# ProProject_PetCareSTM32_MiniSTM32_2024-0.net
KiCad netlist of a schematic drawn in EasyEDA Pro
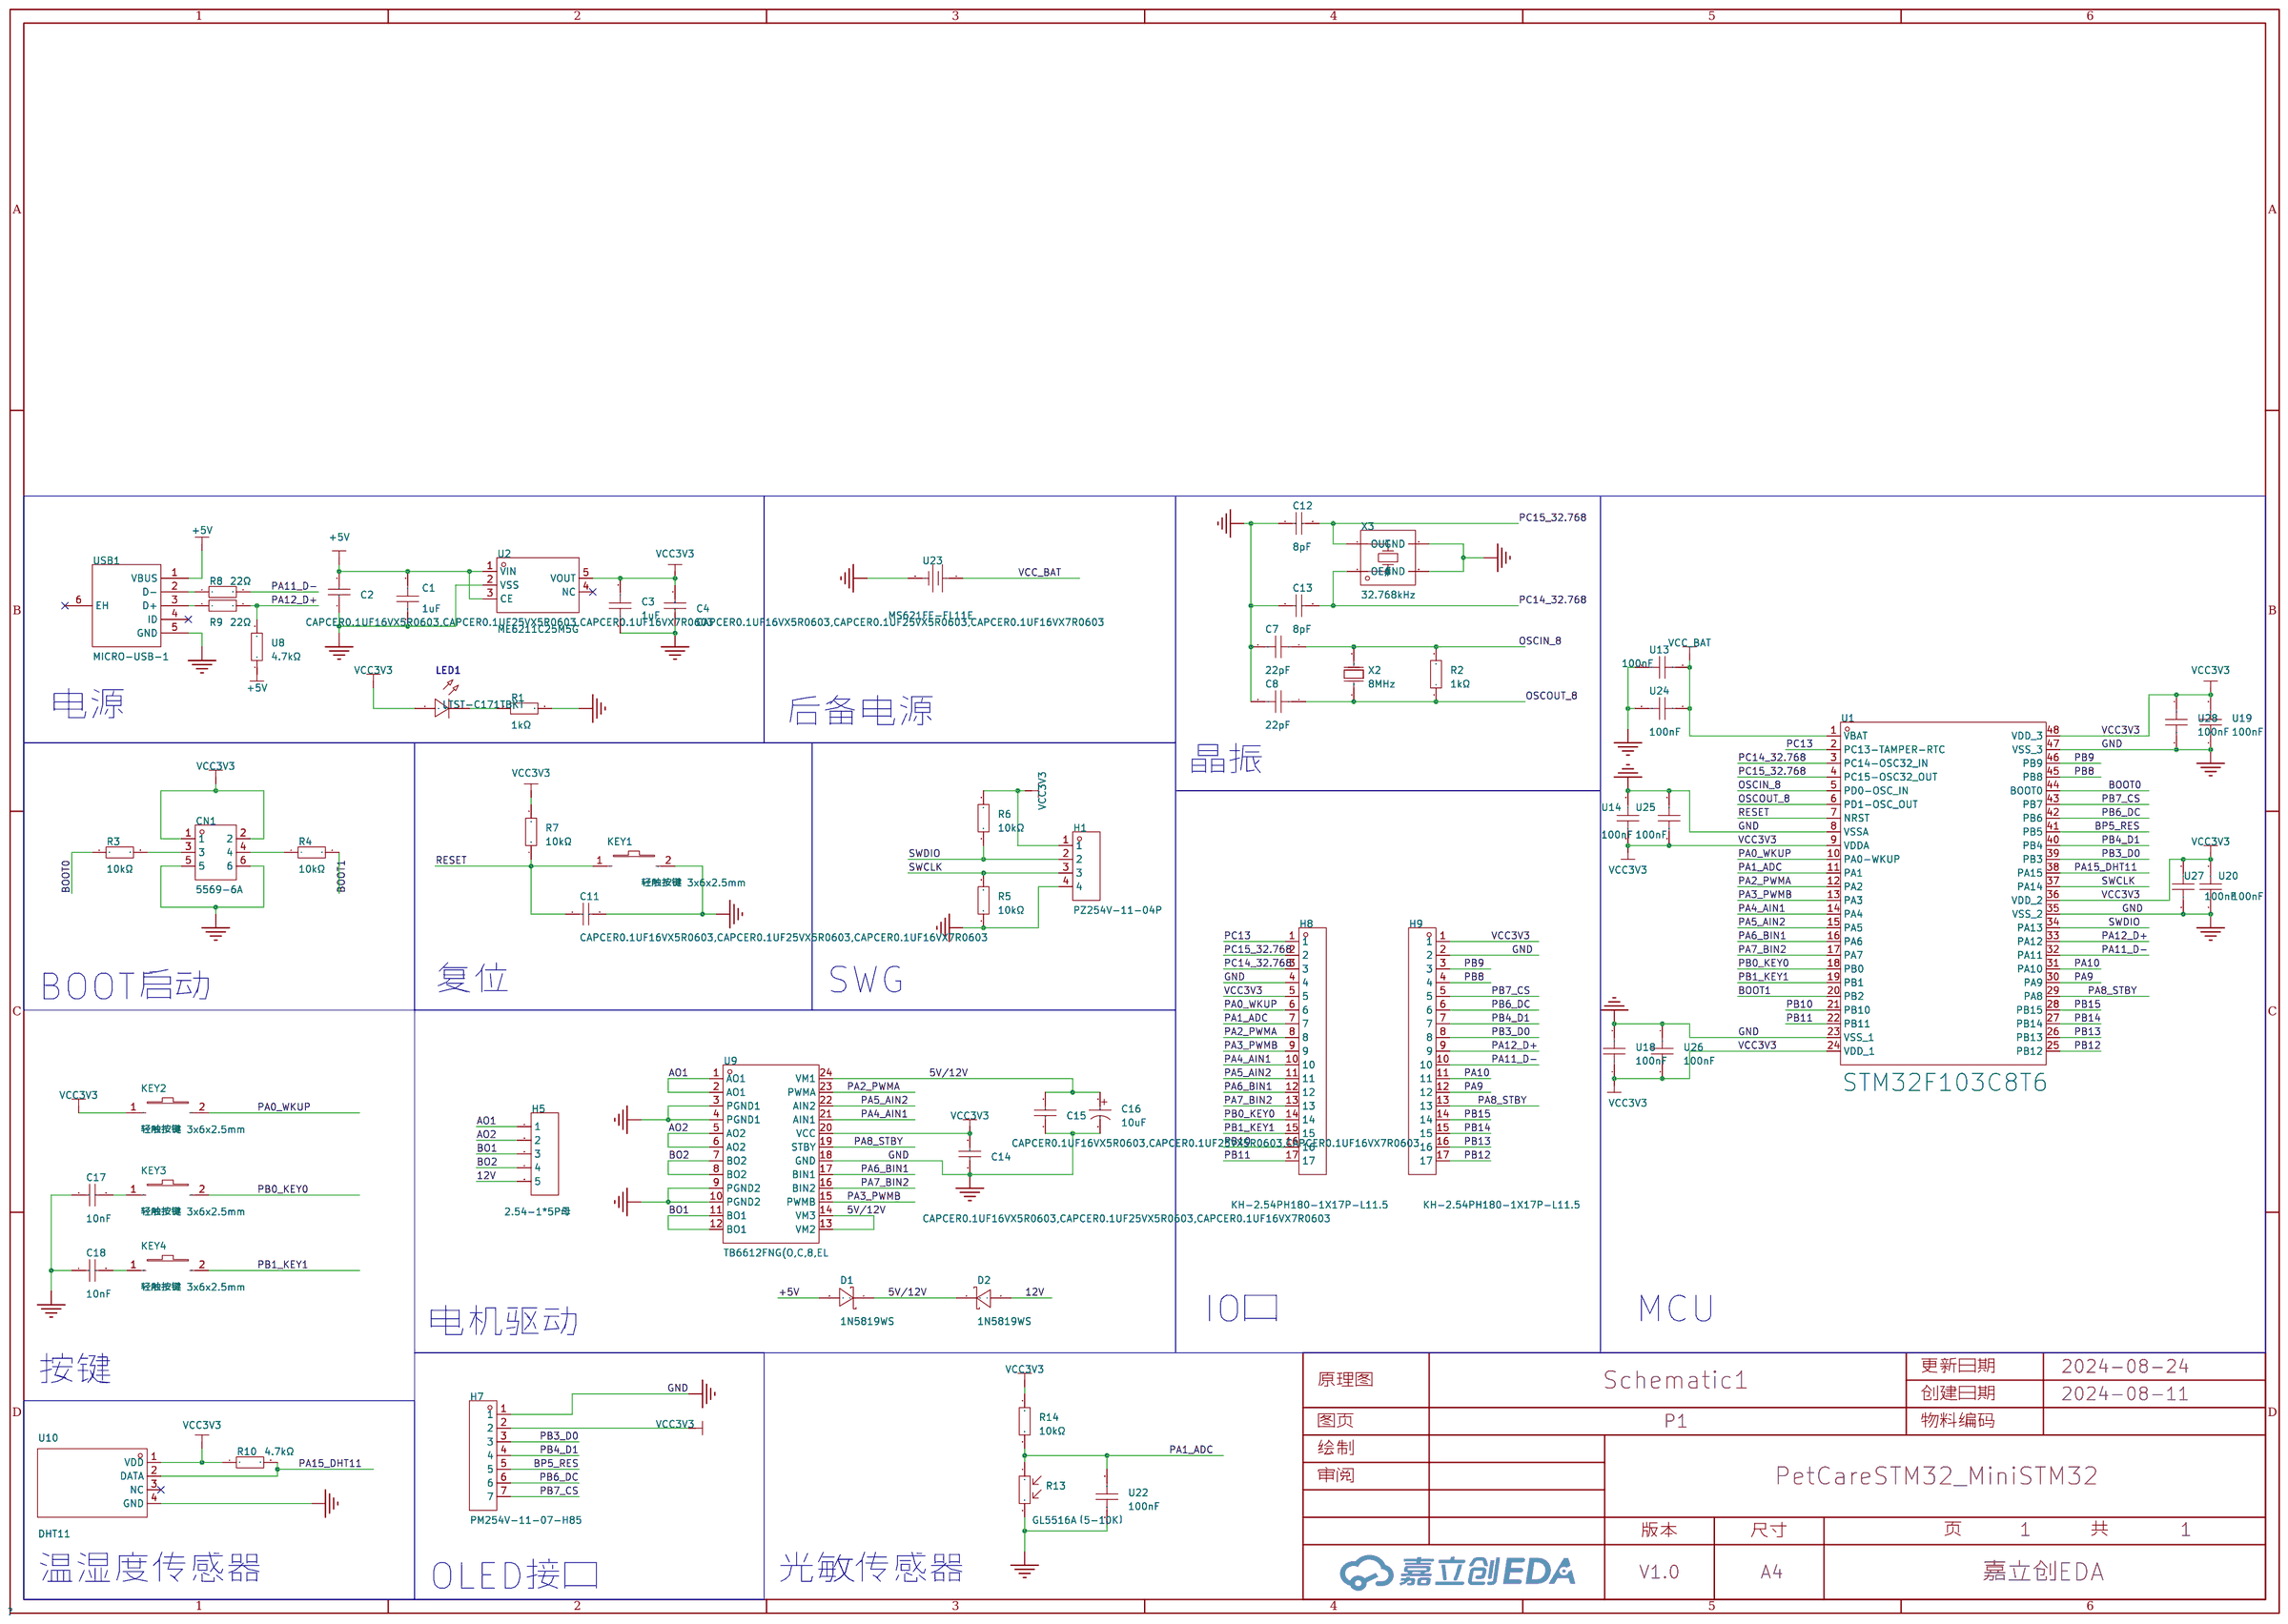
[diagram p0: schematic sheet]

(export (version "E")
  (design (tool "Eeschema 10.0.6"))
  (components
    (comp (ref "C1")
      (value "1uF")
      (footprint "easyedapro:C0603")
      (description "容值:1uF;精度:±10%;额定电压:50V;材质(温度系数):X5R;")
      (fields
        (field (name "Manufacturer Part") "CL10A105KB8NNNC")
        (field (name "Manufacturer") "SAMSUNG(三星)")
      )
      (libsource (lib "easyedapro") (part "CL10A105KB8NNNC"))
    )
    (comp (ref "C2")
      (value "CAPCER0.1UF16VX5R0603,CAPCER0.1UF25VX5R0603,CAPCER0.1UF16VX7R0603")
      (footprint "easyedapro:C0603")
      (libsource (lib "easyedapro") (part "CAPCER0.1UF16VX5R0603,CAPCER0.1UF25VX5R0603,CAPCER0.1UF16VX7R0603"))
    )
    (comp (ref "C3")
      (value "1uF")
      (footprint "easyedapro:C0603")
      (description "容值:1uF;精度:±10%;额定电压:50V;材质(温度系数):X5R;")
      (fields
        (field (name "Manufacturer Part") "CL10A105KB8NNNC")
        (field (name "Manufacturer") "SAMSUNG(三星)")
      )
      (libsource (lib "easyedapro") (part "CL10A105KB8NNNC"))
    )
    (comp (ref "C4")
      (value "CAPCER0.1UF16VX5R0603,CAPCER0.1UF25VX5R0603,CAPCER0.1UF16VX7R0603")
      (footprint "easyedapro:C0603")
      (libsource (lib "easyedapro") (part "CAPCER0.1UF16VX5R0603,CAPCER0.1UF25VX5R0603,CAPCER0.1UF16VX7R0603"))
    )
    (comp (ref "C7")
      (value "22pF")
      (footprint "easyedapro:C0603")
      (description "容值:22pF;精度:±5%;额定电压:50V;材质(温度系数):C0G;")
      (fields
        (field (name "Manufacturer Part") "CL10C220JB81PNC")
        (field (name "Manufacturer") "SAMSUNG(三星)")
      )
      (libsource (lib "easyedapro") (part "CL10C220JB81PNC"))
    )
    (comp (ref "C8")
      (value "22pF")
      (footprint "easyedapro:C0603")
      (description "容值:22pF;精度:±5%;额定电压:50V;材质(温度系数):C0G;")
      (fields
        (field (name "Manufacturer Part") "CL10C220JB81PNC")
        (field (name "Manufacturer") "SAMSUNG(三星)")
      )
      (libsource (lib "easyedapro") (part "CL10C220JB81PNC"))
    )
    (comp (ref "C11")
      (value "CAPCER0.1UF16VX5R0603,CAPCER0.1UF25VX5R0603,CAPCER0.1UF16VX7R0603")
      (footprint "easyedapro:C0603")
      (libsource (lib "easyedapro") (part "CAPCER0.1UF16VX5R0603,CAPCER0.1UF25VX5R0603,CAPCER0.1UF16VX7R0603"))
    )
    (comp (ref "C12")
      (value "8pF")
      (footprint "easyedapro:C0603")
      (description "容值:8pF;额定电压:50V;材质(温度系数):C0G;")
      (fields (field (name "Manufacturer Part") "0603CG8R0C500NT") (field (name "Manufacturer") "FH(风华)"))
      (libsource (lib "easyedapro") (part "0603CG8R0C500NT_C36508"))
    )
    (comp (ref "C13")
      (value "8pF")
      (footprint "easyedapro:C0603")
      (description "容值:8pF;额定电压:50V;材质(温度系数):C0G;")
      (fields (field (name "Manufacturer Part") "0603CG8R0C500NT") (field (name "Manufacturer") "FH(风华)"))
      (libsource (lib "easyedapro") (part "0603CG8R0C500NT_C36508"))
    )
    (comp (ref "C14")
      (value "CAPCER0.1UF16VX5R0603,CAPCER0.1UF25VX5R0603,CAPCER0.1UF16VX7R0603")
      (footprint "easyedapro:C0603")
      (libsource (lib "easyedapro") (part "CAPCER0.1UF16VX5R0603,CAPCER0.1UF25VX5R0603,CAPCER0.1UF16VX7R0603"))
    )
    (comp (ref "C15")
      (value "CAPCER0.1UF16VX5R0603,CAPCER0.1UF25VX5R0603,CAPCER0.1UF16VX7R0603")
      (footprint "easyedapro:C0603")
      (libsource (lib "easyedapro") (part "CAPCER0.1UF16VX5R0603,CAPCER0.1UF25VX5R0603,CAPCER0.1UF16VX7R0603"))
    )
    (comp (ref "C16")
      (value "10uF")
      (footprint "easyedapro:CAP-TH_BD5.0-P2.00-D0.8-FD")
      (description "容值:10uF;精度:±20%;额定电压:25V;")
      (fields (field (name "Manufacturer Part") "KF100M025C110A") (field (name "Manufacturer") "CapXon(丰宾)"))
      (libsource (lib "easyedapro") (part "KF100M025C110A"))
    )
    (comp (ref "C17")
      (value "10nF")
      (footprint "easyedapro:C0603")
      (description "容值:10nF;精度:±10%;额定电压:50V;材质(温度系数):X7R;")
      (fields
        (field (name "Manufacturer Part") "CC0603KRX7R9BB103")
        (field (name "Manufacturer") "YAGEO(国巨)")
      )
      (libsource (lib "easyedapro") (part "CC0603KRX7R9BB103"))
    )
    (comp (ref "C18")
      (value "10nF")
      (footprint "easyedapro:C0603")
      (description "容值:10nF;精度:±10%;额定电压:50V;材质(温度系数):X7R;")
      (fields
        (field (name "Manufacturer Part") "CC0603KRX7R9BB103")
        (field (name "Manufacturer") "YAGEO(国巨)")
      )
      (libsource (lib "easyedapro") (part "CC0603KRX7R9BB103"))
    )
    (comp (ref "CN1")
      (value "5569-6A")
      (footprint "easyedapro:CONN-TH_6P-P4.20_5569-6A-1")
      (libsource (lib "easyedapro") (part "5569-6A"))
    )
    (comp (ref "D1")
      (value "1N5819WS")
      (footprint "easyedapro:SOD-323_L1.8-W1.3-LS2.5-RD")
      (description "正向压降(Vf):600mV@1A;直流反向耐压(Vr):40V;平均整流电流(Io):1A;")
      (fields (field (name "Manufacturer") "Hottech(合科泰)"))
      (libsource (lib "easyedapro") (part "1N5819WS"))
    )
    (comp (ref "D2")
      (value "1N5819WS")
      (footprint "easyedapro:SOD-323_L1.8-W1.3-LS2.5-RD")
      (description "正向压降(Vf):600mV@1A;直流反向耐压(Vr):40V;平均整流电流(Io):1A;")
      (fields (field (name "Manufacturer") "Hottech(合科泰)"))
      (libsource (lib "easyedapro") (part "1N5819WS"))
    )
    (comp (ref "H1")
      (value "PZ254V-11-04P")
      (footprint "easyedapro:HDR-TH_4P-P2.54-V-M")
      (fields (field (name "Manufacturer") "XFCN(兴飞)"))
      (libsource (lib "easyedapro") (part "PZ254V-11-04P_C2691448"))
    )
    (comp (ref "H5")
      (value "2.54-1*5P母")
      (footprint "easyedapro:HDR-TH_5P-P2.54-V-F")
      (description "插孔结构:1x5P;间距:2.54mm;行距:-;安装类型:直插;排数:单排;总孔位数:5P;塑高:-;触头材质:-;触头镀层:-;")
      (fields (field (name "Manufacturer") "BOOMELE(博穆精密)"))
      (libsource (lib "easyedapro") (part "Header-Female-2.54_1x5"))
    )
    (comp (ref "H7")
      (value "PM254V-11-07-H85")
      (footprint "easyedapro:HDR-TH_7P-P2.54-V-F")
      (fields (field (name "Manufacturer") "XFCN(兴飞)"))
      (libsource (lib "easyedapro") (part "PM254V-11-07-H85"))
    )
    (comp (ref "H8")
      (value "KH-2.54PH180-1X17P-L11.5")
      (footprint "easyedapro:HDR-TH_17P-P2.54-V-M")
      (fields (field (name "Manufacturer") "kinghelm(金航标)"))
      (libsource (lib "easyedapro") (part "KH-2.54PH180-1X17P-L11.5"))
    )
    (comp (ref "H9")
      (value "KH-2.54PH180-1X17P-L11.5")
      (footprint "easyedapro:HDR-TH_17P-P2.54-V-M")
      (fields (field (name "Manufacturer") "kinghelm(金航标)"))
      (libsource (lib "easyedapro") (part "KH-2.54PH180-1X17P-L11.5"))
    )
    (comp (ref "KEY1")
      (value "轻触按键 3x6x2.5mm")
      (footprint "easyedapro:SW-SMD_L6.0-W3.6-LS8.0")
      (libsource (lib "easyedapro") (part "3x6x2.5mm"))
    )
    (comp (ref "KEY2")
      (value "轻触按键 3x6x2.5mm")
      (footprint "easyedapro:SW-SMD_L6.0-W3.6-LS8.0")
      (libsource (lib "easyedapro") (part "3x6x2.5mm"))
    )
    (comp (ref "KEY3")
      (value "轻触按键 3x6x2.5mm")
      (footprint "easyedapro:SW-SMD_L6.0-W3.6-LS8.0")
      (libsource (lib "easyedapro") (part "3x6x2.5mm"))
    )
    (comp (ref "KEY4")
      (value "轻触按键 3x6x2.5mm")
      (footprint "easyedapro:SW-SMD_L6.0-W3.6-LS8.0")
      (libsource (lib "easyedapro") (part "3x6x2.5mm"))
    )
    (comp (ref "LED1")
      (value "LTST-C171TBKT")
      (footprint "easyedapro:LED_0805")
      (fields (field (name "Manufacturer") "LITEON(光宝)"))
      (libsource (lib "easyedapro") (part "LED_B"))
    )
    (comp (ref "R1")
      (value "1kΩ")
      (footprint "easyedapro:R0603")
      (description "电阻类型:厚膜电阻;阻值:1kΩ;精度:±1%;功率:100mW;最大工作电压:75V;温度系数:±100ppm/°C;")
      (fields (field (name "Manufacturer Part") "RC0603FR-071KL") (field (name "Manufacturer") "YAGEO(国巨)"))
      (libsource (lib "easyedapro") (part "RC0603FR-071KL"))
    )
    (comp (ref "R2")
      (value "1kΩ")
      (footprint "easyedapro:R0603")
      (description "电阻类型:厚膜电阻;阻值:1kΩ;精度:±0.5%;功率:100mW;最大工作电压:75V;温度系数:±100ppm/°C;")
      (fields
        (field (name "Manufacturer Part") "0603WAD1001T5E")
        (field (name "Manufacturer") "UNI-ROYAL(厚声)")
      )
      (libsource (lib "easyedapro") (part "0603WAD1001T5E"))
    )
    (comp (ref "R3")
      (value "10kΩ")
      (footprint "easyedapro:R0603")
      (description "电阻类型:厚膜电阻;阻值:10kΩ;精度:±1%;功率:100mW;最大工作电压:75V;温度系数:±100ppm/°C;")
      (fields
        (field (name "Manufacturer Part") "0603WAF1002T5E")
        (field (name "Manufacturer") "UNI-ROYAL(厚声)")
      )
      (libsource (lib "easyedapro") (part "0603WAF1002T5E"))
    )
    (comp (ref "R4")
      (value "10kΩ")
      (footprint "easyedapro:R0603")
      (description "电阻类型:厚膜电阻;阻值:10kΩ;精度:±1%;功率:100mW;最大工作电压:75V;温度系数:±100ppm/°C;")
      (fields
        (field (name "Manufacturer Part") "0603WAF1002T5E")
        (field (name "Manufacturer") "UNI-ROYAL(厚声)")
      )
      (libsource (lib "easyedapro") (part "0603WAF1002T5E"))
    )
    (comp (ref "R5")
      (value "10kΩ")
      (footprint "easyedapro:R0603")
      (description "电阻类型:厚膜电阻;阻值:10kΩ;精度:±1%;功率:100mW;最大工作电压:75V;温度系数:±100ppm/°C;")
      (fields
        (field (name "Manufacturer Part") "0603WAF1002T5E")
        (field (name "Manufacturer") "UNI-ROYAL(厚声)")
      )
      (libsource (lib "easyedapro") (part "0603WAF1002T5E"))
    )
    (comp (ref "R6")
      (value "10kΩ")
      (footprint "easyedapro:R0603")
      (description "电阻类型:厚膜电阻;阻值:10kΩ;精度:±1%;功率:100mW;最大工作电压:75V;温度系数:±100ppm/°C;")
      (fields
        (field (name "Manufacturer Part") "0603WAF1002T5E")
        (field (name "Manufacturer") "UNI-ROYAL(厚声)")
      )
      (libsource (lib "easyedapro") (part "0603WAF1002T5E"))
    )
    (comp (ref "R7")
      (value "10kΩ")
      (footprint "easyedapro:R0603")
      (description "电阻类型:厚膜电阻;阻值:10kΩ;精度:±1%;功率:100mW;最大工作电压:75V;温度系数:±100ppm/°C;")
      (fields
        (field (name "Manufacturer Part") "0603WAF1002T5E")
        (field (name "Manufacturer") "UNI-ROYAL(厚声)")
      )
      (libsource (lib "easyedapro") (part "0603WAF1002T5E"))
    )
    (comp (ref "R8")
      (value "22Ω")
      (footprint "easyedapro:R0805")
      (description "电阻类型:薄膜电阻;阻值:22Ω;精度:±1%;功率:250mW;最大工作电压:150V;温度系数:±25ppm/°C;")
      (fields
        (field (name "Manufacturer Part") "TC0525F220JT5E")
        (field (name "Manufacturer") "UNI-ROYAL(厚声)")
      )
      (libsource (lib "easyedapro") (part "TC0525F220JT5E"))
    )
    (comp (ref "R9")
      (value "22Ω")
      (footprint "easyedapro:R0805")
      (description "电阻类型:薄膜电阻;阻值:22Ω;精度:±1%;功率:250mW;最大工作电压:150V;温度系数:±25ppm/°C;")
      (fields
        (field (name "Manufacturer Part") "TC0525F220JT5E")
        (field (name "Manufacturer") "UNI-ROYAL(厚声)")
      )
      (libsource (lib "easyedapro") (part "TC0525F220JT5E"))
    )
    (comp (ref "R10")
      (value "4.7kΩ")
      (footprint "easyedapro:R1206")
      (description "电阻类型:厚膜电阻;阻值:4.7kΩ;精度:±1%;功率:250mW;最大工作电压:200V;温度系数:±100ppm/°C;")
      (fields
        (field (name "Manufacturer Part") "1206W4F4701T5E")
        (field (name "Manufacturer") "UNI-ROYAL(厚声)")
      )
      (libsource (lib "easyedapro") (part "1206W4F4701T5E"))
    )
    (comp (ref "R13")
      (value "GL5516A（5-10K）")
      (footprint "easyedapro:RES-TH_L5.1-W4.3-P3.40_GL55")
      (description "暗电阻:200kΩ;亮电阻 @ 10Lux:5kΩ~10kΩ;光谱峰值(波长):540nm;")
      (fields (field (name "Manufacturer") "JCHL(晶创和立)"))
      (libsource (lib "easyedapro") (part "GL5516A(5-10K)"))
    )
    (comp (ref "R14")
      (value "10kΩ")
      (footprint "easyedapro:R0603")
      (description "电阻类型:厚膜电阻;阻值:10kΩ;精度:±1%;功率:100mW;最大工作电压:75V;温度系数:±100ppm/°C;")
      (fields
        (field (name "Manufacturer Part") "0603WAF1002T5E")
        (field (name "Manufacturer") "UNI-ROYAL(厚声)")
      )
      (libsource (lib "easyedapro") (part "0603WAF1002T5E"))
    )
    (comp (ref "U1")
      (value "STM32F103C8T6")
      (footprint "easyedapro:LQFP-48_L7.0-W7.0-P0.50-LS9.0-BL")
      (description "CPU内核:ARM-M3;程序存储容量:64KB;RAM总容量:20KB;GPIO端口数量:37;工作电压范围:2V~3.6V;CPU最大主频:72MHz;程序存储器类型:FLASH;")
      (fields (field (name "Manufacturer") "ST(意法半导体)"))
      (libsource (lib "easyedapro") (part "STM32F103C8T6"))
    )
    (comp (ref "U2")
      (value "ME6211C25M5G")
      (footprint "easyedapro:SOT-23-5_L2.9-W1.7-P0.95-LS2.8-BL")
      (fields (field (name "Manufacturer") "MICRONE(南京微盟)"))
      (libsource (lib "easyedapro") (part "ME6211C25M5G"))
    )
    (comp (ref "U8")
      (value "4.7kΩ")
      (footprint "easyedapro:R0603")
      (description "电阻类型:薄膜电阻;阻值:4.7kΩ;精度:±1%;功率:100mW;最大工作电压:75V;温度系数:±50ppm/°C;")
      (fields (field (name "Manufacturer Part") "AR03FTDX4701A") (field (name "Manufacturer") "Viking(光颉)"))
      (libsource (lib "easyedapro") (part "AR03FTDX4701A"))
    )
    (comp (ref "U9")
      (value "TB6612FNG(O,C,8,EL")
      (footprint "easyedapro:SSOP-24_L8.4-W5.8-P0.65-LS7.8-BL")
      (description "双直流电机驱动器集成电路")
      (fields (field (name "Manufacturer") "TOSHIBA(东芝)"))
      (libsource (lib "easyedapro") (part "TB6612FNG(O,C,8,EL"))
    )
    (comp (ref "U10")
      (value "DHT11")
      (footprint "easyedapro:SENSOR-TH_DHT11")
      (description "新款电容式数字温湿度传感器,老款已停产16.1x12.6x5.8mm")
      (fields (field (name "Manufacturer") "广州奥松"))
      (libsource (lib "easyedapro") (part "DHT11"))
    )
    (comp (ref "U13")
      (value "100nF")
      (footprint "easyedapro:C0603")
      (description "容值:100nF;精度:±10%;额定电压:50V;材质(温度系数):X7R;")
      (fields
        (field (name "Manufacturer Part") "CGA0603X7R104K500JT")
        (field (name "Manufacturer") "HRE(芯声)")
      )
      (libsource (lib "easyedapro") (part "CGA0603X7R104K500JT"))
    )
    (comp (ref "U14")
      (value "100nF")
      (footprint "easyedapro:C0603")
      (description "容值:100nF;精度:±10%;额定电压:50V;材质(温度系数):X7R;")
      (fields
        (field (name "Manufacturer Part") "CGA0603X7R104K500JT")
        (field (name "Manufacturer") "HRE(芯声)")
      )
      (libsource (lib "easyedapro") (part "CGA0603X7R104K500JT"))
    )
    (comp (ref "U18")
      (value "100nF")
      (footprint "easyedapro:C0603")
      (description "容值:100nF;精度:±10%;额定电压:50V;材质(温度系数):X7R;")
      (fields
        (field (name "Manufacturer Part") "CGA0603X7R104K500JT")
        (field (name "Manufacturer") "HRE(芯声)")
      )
      (libsource (lib "easyedapro") (part "CGA0603X7R104K500JT"))
    )
    (comp (ref "U19")
      (value "100nF")
      (footprint "easyedapro:C0603")
      (description "容值:100nF;精度:±10%;额定电压:50V;材质(温度系数):X7R;")
      (fields
        (field (name "Manufacturer Part") "CGA0603X7R104K500JT")
        (field (name "Manufacturer") "HRE(芯声)")
      )
      (libsource (lib "easyedapro") (part "CGA0603X7R104K500JT"))
    )
    (comp (ref "U20")
      (value "100nF")
      (footprint "easyedapro:C0603")
      (description "容值:100nF;精度:±10%;额定电压:50V;材质(温度系数):X7R;")
      (fields
        (field (name "Manufacturer Part") "CGA0603X7R104K500JT")
        (field (name "Manufacturer") "HRE(芯声)")
      )
      (libsource (lib "easyedapro") (part "CGA0603X7R104K500JT"))
    )
    (comp (ref "U22")
      (value "100nF")
      (footprint "easyedapro:C0603")
      (description "容值:100nF;精度:±10%;额定电压:50V;材质(温度系数):X7R;")
      (fields
        (field (name "Manufacturer Part") "CGA0603X7R104K500JT")
        (field (name "Manufacturer") "HRE(芯声)")
      )
      (libsource (lib "easyedapro") (part "CGA0603X7R104K500JT"))
    )
    (comp (ref "U23")
      (value "MS621FE-FL11E")
      (footprint "easyedapro:BAT-SMD_FL11E")
      (description "FL11E 3.3V可充电纽扣电池 5.5mAH")
      (fields (field (name "Manufacturer") "Seiko(精工)"))
      (libsource (lib "easyedapro") (part "MS621FE-FL11E"))
    )
    (comp (ref "U24")
      (value "100nF")
      (footprint "easyedapro:C0603")
      (description "容值:100nF;精度:±10%;额定电压:50V;材质(温度系数):X7R;")
      (fields
        (field (name "Manufacturer Part") "CGA0603X7R104K500JT")
        (field (name "Manufacturer") "HRE(芯声)")
      )
      (libsource (lib "easyedapro") (part "CGA0603X7R104K500JT"))
    )
    (comp (ref "U25")
      (value "100nF")
      (footprint "easyedapro:C0603")
      (description "容值:100nF;精度:±10%;额定电压:50V;材质(温度系数):X7R;")
      (fields
        (field (name "Manufacturer Part") "CGA0603X7R104K500JT")
        (field (name "Manufacturer") "HRE(芯声)")
      )
      (libsource (lib "easyedapro") (part "CGA0603X7R104K500JT"))
    )
    (comp (ref "U26")
      (value "100nF")
      (footprint "easyedapro:C0603")
      (description "容值:100nF;精度:±10%;额定电压:50V;材质(温度系数):X7R;")
      (fields
        (field (name "Manufacturer Part") "CGA0603X7R104K500JT")
        (field (name "Manufacturer") "HRE(芯声)")
      )
      (libsource (lib "easyedapro") (part "CGA0603X7R104K500JT"))
    )
    (comp (ref "U27")
      (value "100nF")
      (footprint "easyedapro:C0603")
      (description "容值:100nF;精度:±10%;额定电压:50V;材质(温度系数):X7R;")
      (fields
        (field (name "Manufacturer Part") "CGA0603X7R104K500JT")
        (field (name "Manufacturer") "HRE(芯声)")
      )
      (libsource (lib "easyedapro") (part "CGA0603X7R104K500JT"))
    )
    (comp (ref "U28")
      (value "100nF")
      (footprint "easyedapro:C0603")
      (description "容值:100nF;精度:±10%;额定电压:50V;材质(温度系数):X7R;")
      (fields
        (field (name "Manufacturer Part") "CGA0603X7R104K500JT")
        (field (name "Manufacturer") "HRE(芯声)")
      )
      (libsource (lib "easyedapro") (part "CGA0603X7R104K500JT"))
    )
    (comp (ref "USB1")
      (value "MICRO-USB-1")
      (footprint "easyedapro:MICRO-USB-SMD_C9900008946")
      (libsource (lib "easyedapro") (part "MICRO-USB-1"))
    )
    (comp (ref "X2")
      (value "8MHz")
      (footprint "easyedapro:OSC-SMD_L5.0-W3.2")
      (description "晶振类型:贴片晶振;频率:8MHz;常温频差:±20ppm;外接负载电容:18pF;频率稳定度(全温):±30ppm;")
      (fields
        (field (name "Manufacturer Part") "ABM3-8.000MHZ-D2Y-T")
        (field (name "Manufacturer") "ABRACON")
      )
      (libsource (lib "easyedapro") (part "ABM3-8.000MHZ-D2Y-T"))
    )
    (comp (ref "X3")
      (value "32.768kHz")
      (footprint "easyedapro:CRYSTAL-SMD_4P-L8.0-W3.8-BL")
      (description "晶振类型:-;频率:32.768kHz;常温频差:±20ppm;外接负载电容:12.5pF;频率稳定度(全温):-;")
      (fields (field (name "Manufacturer Part") "ABS25-32.768KHZ-T") (field (name "Manufacturer") "ABRACON"))
      (libsource (lib "easyedapro") (part "ABS25-32.768KHZ-T"))
    )
  )
  (nets
    (net (code "1") (name "+5V") (class "Default")
      (node (ref "C1") (pin "2") (pinfunction "2_2") (pintype "unspecified"))
      (node (ref "C2") (pin "2") (pinfunction "2_2") (pintype "input"))
      (node (ref "D1") (pin "2") (pinfunction "A_2") (pintype "unspecified"))
      (node (ref "U2") (pin "1") (pinfunction "VIN_1") (pintype "unspecified"))
      (node (ref "U2") (pin "3") (pinfunction "CE_3") (pintype "unspecified"))
      (node (ref "U8") (pin "1") (pinfunction "1_1") (pintype "unspecified"))
      (node (ref "USB1") (pin "1") (pinfunction "VBUS_1") (pintype "input"))
    )
    (net (code "2") (name "/5V{slash}12V") (class "Default")
      (node (ref "C15") (pin "2") (pinfunction "2_2") (pintype "input"))
      (node (ref "C16") (pin "1") (pinfunction "1_1") (pintype "input"))
      (node (ref "D1") (pin "1") (pinfunction "K_1") (pintype "unspecified"))
      (node (ref "D2") (pin "1") (pinfunction "K_1") (pintype "unspecified"))
      (node (ref "U9") (pin "13") (pinfunction "VM2_13") (pintype "unspecified"))
      (node (ref "U9") (pin "14") (pinfunction "VM3_14") (pintype "unspecified"))
      (node (ref "U9") (pin "24") (pinfunction "VM1_24") (pintype "unspecified"))
    )
    (net (code "3") (name "/12V") (class "Default")
      (node (ref "D2") (pin "2") (pinfunction "A_2") (pintype "unspecified"))
      (node (ref "H5") (pin "5") (pinfunction "5_5") (pintype "input"))
    )
    (net (code "4") (name "/AO1") (class "Default")
      (node (ref "H5") (pin "1") (pinfunction "1_1") (pintype "input"))
      (node (ref "U9") (pin "1") (pinfunction "AO1_1") (pintype "unspecified"))
      (node (ref "U9") (pin "2") (pinfunction "AO1_2") (pintype "unspecified"))
    )
    (net (code "5") (name "/AO2") (class "Default")
      (node (ref "H5") (pin "2") (pinfunction "2_2") (pintype "input"))
      (node (ref "U9") (pin "5") (pinfunction "AO2_5") (pintype "unspecified"))
      (node (ref "U9") (pin "6") (pinfunction "AO2_6") (pintype "unspecified"))
    )
    (net (code "6") (name "/BO1") (class "Default")
      (node (ref "H5") (pin "3") (pinfunction "3_3") (pintype "input"))
      (node (ref "U9") (pin "11") (pinfunction "BO1_11") (pintype "unspecified"))
      (node (ref "U9") (pin "12") (pinfunction "BO1_12") (pintype "unspecified"))
    )
    (net (code "7") (name "/BO2") (class "Default")
      (node (ref "H5") (pin "4") (pinfunction "4_4") (pintype "input"))
      (node (ref "U9") (pin "7") (pinfunction "BO2_7") (pintype "unspecified"))
      (node (ref "U9") (pin "8") (pinfunction "BO2_8") (pintype "unspecified"))
    )
    (net (code "8") (name "/BOOT0") (class "Default")
      (node (ref "R3") (pin "1") (pinfunction "1_1") (pintype "input"))
      (node (ref "U1") (pin "44") (pinfunction "BOOT0_44") (pintype "unspecified"))
    )
    (net (code "9") (name "/BOOT1") (class "Default")
      (node (ref "R4") (pin "2") (pinfunction "2_2") (pintype "input"))
      (node (ref "U1") (pin "20") (pinfunction "PB2_20") (pintype "unspecified"))
    )
    (net (code "10") (name "/BP5_RES") (class "Default")
      (node (ref "H7") (pin "5") (pinfunction "5_5") (pintype "unspecified"))
      (node (ref "U1") (pin "41") (pinfunction "PB5_41") (pintype "unspecified"))
    )
    (net (code "11") (name "/OSCIN_8") (class "Default")
      (node (ref "C7") (pin "1") (pinfunction "1_1") (pintype "unspecified"))
      (node (ref "R2") (pin "2") (pinfunction "2_2") (pintype "input"))
      (node (ref "U1") (pin "5") (pinfunction "PD0-OSC_IN_5") (pintype "unspecified"))
      (node (ref "X2") (pin "2") (pinfunction "OSC2_2") (pintype "input"))
    )
    (net (code "12") (name "/OSCOUT_8") (class "Default")
      (node (ref "C8") (pin "1") (pinfunction "1_1") (pintype "unspecified"))
      (node (ref "R2") (pin "1") (pinfunction "1_1") (pintype "input"))
      (node (ref "U1") (pin "6") (pinfunction "PD1-OSC_OUT_6") (pintype "unspecified"))
      (node (ref "X2") (pin "1") (pinfunction "OSC1_1") (pintype "input"))
    )
    (net (code "13") (name "/PA0_WKUP") (class "Default")
      (node (ref "H8") (pin "6") (pinfunction "6_6") (pintype "unspecified"))
      (node (ref "KEY2") (pin "2") (pinfunction "2_2") (pintype "input"))
      (node (ref "U1") (pin "10") (pinfunction "PA0-WKUP_10") (pintype "unspecified"))
    )
    (net (code "14") (name "/PA1_ADC") (class "Default")
      (node (ref "H8") (pin "7") (pinfunction "7_7") (pintype "unspecified"))
      (node (ref "R13") (pin "1") (pinfunction "1_1") (pintype "input"))
      (node (ref "R14") (pin "1") (pinfunction "1_1") (pintype "input"))
      (node (ref "U1") (pin "11") (pinfunction "PA1_11") (pintype "unspecified"))
      (node (ref "U22") (pin "2") (pinfunction "2_2") (pintype "unspecified"))
    )
    (net (code "15") (name "/PA2_PWMA") (class "Default")
      (node (ref "H8") (pin "8") (pinfunction "8_8") (pintype "unspecified"))
      (node (ref "U1") (pin "12") (pinfunction "PA2_12") (pintype "unspecified"))
      (node (ref "U9") (pin "23") (pinfunction "PWMA_23") (pintype "unspecified"))
    )
    (net (code "16") (name "/PA3_PWMB") (class "Default")
      (node (ref "H8") (pin "9") (pinfunction "9_9") (pintype "unspecified"))
      (node (ref "U1") (pin "13") (pinfunction "PA3_13") (pintype "unspecified"))
      (node (ref "U9") (pin "15") (pinfunction "PWMB_15") (pintype "unspecified"))
    )
    (net (code "17") (name "/PA4_AIN1") (class "Default")
      (node (ref "H8") (pin "10") (pinfunction "10_10") (pintype "unspecified"))
      (node (ref "U1") (pin "14") (pinfunction "PA4_14") (pintype "unspecified"))
      (node (ref "U9") (pin "21") (pinfunction "AIN1_21") (pintype "unspecified"))
    )
    (net (code "18") (name "/PA5_AIN2") (class "Default")
      (node (ref "H8") (pin "11") (pinfunction "11_11") (pintype "unspecified"))
      (node (ref "U1") (pin "15") (pinfunction "PA5_15") (pintype "unspecified"))
      (node (ref "U9") (pin "22") (pinfunction "AIN2_22") (pintype "unspecified"))
    )
    (net (code "19") (name "/PA6_BIN1") (class "Default")
      (node (ref "H8") (pin "12") (pinfunction "12_12") (pintype "unspecified"))
      (node (ref "U1") (pin "16") (pinfunction "PA6_16") (pintype "unspecified"))
      (node (ref "U9") (pin "17") (pinfunction "BIN1_17") (pintype "unspecified"))
    )
    (net (code "20") (name "/PA7_BIN2") (class "Default")
      (node (ref "H8") (pin "13") (pinfunction "13_13") (pintype "unspecified"))
      (node (ref "U1") (pin "17") (pinfunction "PA7_17") (pintype "unspecified"))
      (node (ref "U9") (pin "16") (pinfunction "BIN2_16") (pintype "unspecified"))
    )
    (net (code "21") (name "/PA8_STBY") (class "Default")
      (node (ref "H9") (pin "13") (pinfunction "13_13") (pintype "unspecified"))
      (node (ref "U1") (pin "29") (pinfunction "PA8_29") (pintype "unspecified"))
      (node (ref "U9") (pin "19") (pinfunction "STBY_19") (pintype "unspecified"))
    )
    (net (code "22") (name "/PA9") (class "Default")
      (node (ref "H9") (pin "12") (pinfunction "12_12") (pintype "unspecified"))
      (node (ref "U1") (pin "30") (pinfunction "PA9_30") (pintype "unspecified"))
    )
    (net (code "23") (name "/PA10") (class "Default")
      (node (ref "H9") (pin "11") (pinfunction "11_11") (pintype "unspecified"))
      (node (ref "U1") (pin "31") (pinfunction "PA10_31") (pintype "unspecified"))
    )
    (net (code "24") (name "/PA11_D-") (class "Default")
      (node (ref "H9") (pin "10") (pinfunction "10_10") (pintype "unspecified"))
      (node (ref "R8") (pin "2") (pinfunction "2_2") (pintype "input"))
      (node (ref "U1") (pin "32") (pinfunction "PA11_32") (pintype "unspecified"))
    )
    (net (code "25") (name "/PA12_D+") (class "Default")
      (node (ref "H9") (pin "9") (pinfunction "9_9") (pintype "unspecified"))
      (node (ref "R9") (pin "2") (pinfunction "2_2") (pintype "input"))
      (node (ref "U1") (pin "33") (pinfunction "PA12_33") (pintype "unspecified"))
      (node (ref "U8") (pin "2") (pinfunction "2_2") (pintype "unspecified"))
    )
    (net (code "26") (name "/PA15_DHT11") (class "Default")
      (node (ref "R10") (pin "2") (pinfunction "2_2") (pintype "input"))
      (node (ref "U1") (pin "38") (pinfunction "PA15_38") (pintype "unspecified"))
      (node (ref "U10") (pin "2") (pinfunction "DATA_2") (pintype "unspecified"))
    )
    (net (code "27") (name "/PB0_KEY0") (class "Default")
      (node (ref "H8") (pin "14") (pinfunction "14_14") (pintype "unspecified"))
      (node (ref "KEY3") (pin "2") (pinfunction "2_2") (pintype "input"))
      (node (ref "U1") (pin "18") (pinfunction "PB0_18") (pintype "unspecified"))
    )
    (net (code "28") (name "/PB1_KEY1") (class "Default")
      (node (ref "H8") (pin "15") (pinfunction "15_15") (pintype "unspecified"))
      (node (ref "KEY4") (pin "2") (pinfunction "2_2") (pintype "input"))
      (node (ref "U1") (pin "19") (pinfunction "PB1_19") (pintype "unspecified"))
    )
    (net (code "29") (name "/PB3_D0") (class "Default")
      (node (ref "H7") (pin "3") (pinfunction "3_3") (pintype "unspecified"))
      (node (ref "H9") (pin "8") (pinfunction "8_8") (pintype "unspecified"))
      (node (ref "U1") (pin "39") (pinfunction "PB3_39") (pintype "unspecified"))
    )
    (net (code "30") (name "/PB4_D1") (class "Default")
      (node (ref "H7") (pin "4") (pinfunction "4_4") (pintype "unspecified"))
      (node (ref "H9") (pin "7") (pinfunction "7_7") (pintype "unspecified"))
      (node (ref "U1") (pin "40") (pinfunction "PB4_40") (pintype "unspecified"))
    )
    (net (code "31") (name "/PB6_DC") (class "Default")
      (node (ref "H7") (pin "6") (pinfunction "6_6") (pintype "unspecified"))
      (node (ref "H9") (pin "6") (pinfunction "6_6") (pintype "unspecified"))
      (node (ref "U1") (pin "42") (pinfunction "PB6_42") (pintype "unspecified"))
    )
    (net (code "32") (name "/PB7_CS") (class "Default")
      (node (ref "H7") (pin "7") (pinfunction "7_7") (pintype "unspecified"))
      (node (ref "H9") (pin "5") (pinfunction "5_5") (pintype "unspecified"))
      (node (ref "U1") (pin "43") (pinfunction "PB7_43") (pintype "unspecified"))
    )
    (net (code "33") (name "/PB8") (class "Default")
      (node (ref "H9") (pin "4") (pinfunction "4_4") (pintype "unspecified"))
      (node (ref "U1") (pin "45") (pinfunction "PB8_45") (pintype "unspecified"))
    )
    (net (code "34") (name "/PB9") (class "Default")
      (node (ref "H9") (pin "3") (pinfunction "3_3") (pintype "unspecified"))
      (node (ref "U1") (pin "46") (pinfunction "PB9_46") (pintype "unspecified"))
    )
    (net (code "35") (name "/PB10") (class "Default")
      (node (ref "H8") (pin "16") (pinfunction "16_16") (pintype "unspecified"))
      (node (ref "U1") (pin "21") (pinfunction "PB10_21") (pintype "unspecified"))
    )
    (net (code "36") (name "/PB11") (class "Default")
      (node (ref "H8") (pin "17") (pinfunction "17_17") (pintype "unspecified"))
      (node (ref "U1") (pin "22") (pinfunction "PB11_22") (pintype "unspecified"))
    )
    (net (code "37") (name "/PB12") (class "Default")
      (node (ref "H9") (pin "17") (pinfunction "17_17") (pintype "unspecified"))
      (node (ref "U1") (pin "25") (pinfunction "PB12_25") (pintype "unspecified"))
    )
    (net (code "38") (name "/PB13") (class "Default")
      (node (ref "H9") (pin "16") (pinfunction "16_16") (pintype "unspecified"))
      (node (ref "U1") (pin "26") (pinfunction "PB13_26") (pintype "unspecified"))
    )
    (net (code "39") (name "/PB14") (class "Default")
      (node (ref "H9") (pin "15") (pinfunction "15_15") (pintype "unspecified"))
      (node (ref "U1") (pin "27") (pinfunction "PB14_27") (pintype "unspecified"))
    )
    (net (code "40") (name "/PB15") (class "Default")
      (node (ref "H9") (pin "14") (pinfunction "14_14") (pintype "unspecified"))
      (node (ref "U1") (pin "28") (pinfunction "PB15_28") (pintype "unspecified"))
    )
    (net (code "41") (name "/PC13") (class "Default")
      (node (ref "H8") (pin "1") (pinfunction "1_1") (pintype "unspecified"))
      (node (ref "U1") (pin "2") (pinfunction "PC13-TAMPER-RTC_2") (pintype "unspecified"))
    )
    (net (code "42") (name "/PC14_32.768") (class "Default")
      (node (ref "C13") (pin "2") (pinfunction "2_2") (pintype "input"))
      (node (ref "H8") (pin "3") (pinfunction "3_3") (pintype "unspecified"))
      (node (ref "U1") (pin "3") (pinfunction "PC14-OSC32_IN_3") (pintype "unspecified"))
      (node (ref "X3") (pin "1") (pinfunction "OE#_1") (pintype "input"))
    )
    (net (code "43") (name "/PC15_32.768") (class "Default")
      (node (ref "C12") (pin "2") (pinfunction "2_2") (pintype "input"))
      (node (ref "H8") (pin "2") (pinfunction "2_2") (pintype "unspecified"))
      (node (ref "U1") (pin "4") (pinfunction "PC15-OSC32_OUT_4") (pintype "unspecified"))
      (node (ref "X3") (pin "4") (pinfunction "OUT_4") (pintype "input"))
    )
    (net (code "44") (name "/RESET") (class "Default")
      (node (ref "C11") (pin "1") (pinfunction "1_1") (pintype "input"))
      (node (ref "KEY1") (pin "1") (pinfunction "1_1") (pintype "input"))
      (node (ref "R7") (pin "1") (pinfunction "1_1") (pintype "input"))
      (node (ref "U1") (pin "7") (pinfunction "NRST_7") (pintype "unspecified"))
    )
    (net (code "45") (name "/SWCLK") (class "Default")
      (node (ref "H1") (pin "3") (pinfunction "3_3") (pintype "unspecified"))
      (node (ref "R5") (pin "2") (pinfunction "2_2") (pintype "input"))
      (node (ref "U1") (pin "37") (pinfunction "PA14_37") (pintype "unspecified"))
    )
    (net (code "46") (name "/SWDIO") (class "Default")
      (node (ref "H1") (pin "2") (pinfunction "2_2") (pintype "unspecified"))
      (node (ref "R6") (pin "1") (pinfunction "1_1") (pintype "input"))
      (node (ref "U1") (pin "34") (pinfunction "PA13_34") (pintype "unspecified"))
    )
    (net (code "47") (name "GND") (class "Default")
      (node (ref "C1") (pin "1") (pinfunction "1_1") (pintype "unspecified"))
      (node (ref "C11") (pin "2") (pinfunction "2_2") (pintype "input"))
      (node (ref "C12") (pin "1") (pinfunction "1_1") (pintype "input"))
      (node (ref "C13") (pin "1") (pinfunction "1_1") (pintype "input"))
      (node (ref "C14") (pin "1") (pinfunction "1_1") (pintype "input"))
      (node (ref "C15") (pin "1") (pinfunction "1_1") (pintype "input"))
      (node (ref "C16") (pin "2") (pinfunction "2_2") (pintype "input"))
      (node (ref "C17") (pin "2") (pinfunction "2_2") (pintype "input"))
      (node (ref "C18") (pin "1") (pinfunction "1_1") (pintype "input"))
      (node (ref "C2") (pin "1") (pinfunction "1_1") (pintype "input"))
      (node (ref "C3") (pin "1") (pinfunction "1_1") (pintype "unspecified"))
      (node (ref "C4") (pin "1") (pinfunction "1_1") (pintype "input"))
      (node (ref "C7") (pin "2") (pinfunction "2_2") (pintype "unspecified"))
      (node (ref "C8") (pin "2") (pinfunction "2_2") (pintype "unspecified"))
      (node (ref "CN1") (pin "5") (pinfunction "5_5") (pintype "unspecified"))
      (node (ref "CN1") (pin "6") (pinfunction "6_6") (pintype "unspecified"))
      (node (ref "H1") (pin "4") (pinfunction "4_4") (pintype "unspecified"))
      (node (ref "H7") (pin "1") (pinfunction "1_1") (pintype "unspecified"))
      (node (ref "H8") (pin "4") (pinfunction "4_4") (pintype "unspecified"))
      (node (ref "H9") (pin "2") (pinfunction "2_2") (pintype "unspecified"))
      (node (ref "KEY1") (pin "2") (pinfunction "2_2") (pintype "input"))
      (node (ref "R1") (pin "2") (pinfunction "2_2") (pintype "input"))
      (node (ref "R13") (pin "2") (pinfunction "2_2") (pintype "input"))
      (node (ref "R5") (pin "1") (pinfunction "1_1") (pintype "input"))
      (node (ref "U1") (pin "23") (pinfunction "VSS_1_23") (pintype "unspecified"))
      (node (ref "U1") (pin "35") (pinfunction "VSS_2_35") (pintype "unspecified"))
      (node (ref "U1") (pin "47") (pinfunction "VSS_3_47") (pintype "unspecified"))
      (node (ref "U1") (pin "8") (pinfunction "VSSA_8") (pintype "unspecified"))
      (node (ref "U10") (pin "4") (pinfunction "GND_4") (pintype "unspecified"))
      (node (ref "U13") (pin "2") (pinfunction "2_2") (pintype "unspecified"))
      (node (ref "U14") (pin "2") (pinfunction "2_2") (pintype "unspecified"))
      (node (ref "U18") (pin "2") (pinfunction "2_2") (pintype "unspecified"))
      (node (ref "U19") (pin "1") (pinfunction "1_1") (pintype "unspecified"))
      (node (ref "U2") (pin "2") (pinfunction "VSS_2") (pintype "unspecified"))
      (node (ref "U20") (pin "1") (pinfunction "1_1") (pintype "unspecified"))
      (node (ref "U22") (pin "1") (pinfunction "1_1") (pintype "unspecified"))
      (node (ref "U23") (pin "2") (pinfunction "-_2") (pintype "unspecified"))
      (node (ref "U24") (pin "2") (pinfunction "2_2") (pintype "unspecified"))
      (node (ref "U25") (pin "1") (pinfunction "1_1") (pintype "unspecified"))
      (node (ref "U26") (pin "1") (pinfunction "1_1") (pintype "unspecified"))
      (node (ref "U27") (pin "2") (pinfunction "2_2") (pintype "unspecified"))
      (node (ref "U28") (pin "2") (pinfunction "2_2") (pintype "unspecified"))
      (node (ref "U9") (pin "10") (pinfunction "PGND2_10") (pintype "unspecified"))
      (node (ref "U9") (pin "18") (pinfunction "GND_18") (pintype "unspecified"))
      (node (ref "U9") (pin "3") (pinfunction "PGND1_3") (pintype "unspecified"))
      (node (ref "U9") (pin "4") (pinfunction "PGND1_4") (pintype "unspecified"))
      (node (ref "U9") (pin "9") (pinfunction "PGND2_9") (pintype "unspecified"))
      (node (ref "USB1") (pin "5") (pinfunction "GND_5") (pintype "input"))
      (node (ref "X3") (pin "2") (pinfunction "GND_2") (pintype "input"))
      (node (ref "X3") (pin "3") (pinfunction "GND_3") (pintype "input"))
    )
    (net (code "48") (name "Net-(C17-Pad1)") (class "Default")
      (node (ref "C17") (pin "1") (pinfunction "1_1") (pintype "input"))
      (node (ref "KEY3") (pin "1") (pinfunction "1_1") (pintype "input"))
    )
    (net (code "49") (name "Net-(C18-Pad2)") (class "Default")
      (node (ref "C18") (pin "2") (pinfunction "2_2") (pintype "input"))
      (node (ref "KEY4") (pin "1") (pinfunction "1_1") (pintype "input"))
    )
    (net (code "50") (name "Net-(CN1-Pad3)") (class "Default")
      (node (ref "CN1") (pin "3") (pinfunction "3_3") (pintype "unspecified"))
      (node (ref "R3") (pin "2") (pinfunction "2_2") (pintype "input"))
    )
    (net (code "51") (name "Net-(CN1-Pad4)") (class "Default")
      (node (ref "CN1") (pin "4") (pinfunction "4_4") (pintype "unspecified"))
      (node (ref "R4") (pin "1") (pinfunction "1_1") (pintype "input"))
    )
    (net (code "52") (name "Net-(LED1-C)") (class "Default")
      (node (ref "LED1") (pin "1") (pinfunction "C_1") (pintype "input"))
      (node (ref "R1") (pin "1") (pinfunction "1_1") (pintype "input"))
    )
    (net (code "53") (name "Net-(USB1-D+)") (class "Default")
      (node (ref "R9") (pin "1") (pinfunction "1_1") (pintype "input"))
      (node (ref "USB1") (pin "3") (pinfunction "D+_3") (pintype "input"))
    )
    (net (code "54") (name "Net-(USB1-D-)") (class "Default")
      (node (ref "R8") (pin "1") (pinfunction "1_1") (pintype "input"))
      (node (ref "USB1") (pin "2") (pinfunction "D-_2") (pintype "input"))
    )
    (net (code "55") (name "VCC3V3") (class "Default")
      (node (ref "C14") (pin "2") (pinfunction "2_2") (pintype "input"))
      (node (ref "C3") (pin "2") (pinfunction "2_2") (pintype "unspecified"))
      (node (ref "C4") (pin "2") (pinfunction "2_2") (pintype "input"))
      (node (ref "CN1") (pin "1") (pinfunction "1_1") (pintype "unspecified"))
      (node (ref "CN1") (pin "2") (pinfunction "2_2") (pintype "unspecified"))
      (node (ref "H1") (pin "1") (pinfunction "1_1") (pintype "unspecified"))
      (node (ref "H7") (pin "2") (pinfunction "2_2") (pintype "unspecified"))
      (node (ref "H8") (pin "5") (pinfunction "5_5") (pintype "unspecified"))
      (node (ref "H9") (pin "1") (pinfunction "1_1") (pintype "unspecified"))
      (node (ref "KEY2") (pin "1") (pinfunction "1_1") (pintype "input"))
      (node (ref "LED1") (pin "2") (pinfunction "A_2") (pintype "input"))
      (node (ref "R10") (pin "1") (pinfunction "1_1") (pintype "input"))
      (node (ref "R14") (pin "2") (pinfunction "2_2") (pintype "input"))
      (node (ref "R6") (pin "2") (pinfunction "2_2") (pintype "input"))
      (node (ref "R7") (pin "2") (pinfunction "2_2") (pintype "input"))
      (node (ref "U1") (pin "24") (pinfunction "VDD_1_24") (pintype "unspecified"))
      (node (ref "U1") (pin "36") (pinfunction "VDD_2_36") (pintype "unspecified"))
      (node (ref "U1") (pin "48") (pinfunction "VDD_3_48") (pintype "unspecified"))
      (node (ref "U1") (pin "9") (pinfunction "VDDA_9") (pintype "unspecified"))
      (node (ref "U10") (pin "1") (pinfunction "VDD_1") (pintype "unspecified"))
      (node (ref "U14") (pin "1") (pinfunction "1_1") (pintype "unspecified"))
      (node (ref "U18") (pin "1") (pinfunction "1_1") (pintype "unspecified"))
      (node (ref "U19") (pin "2") (pinfunction "2_2") (pintype "unspecified"))
      (node (ref "U2") (pin "5") (pinfunction "VOUT_5") (pintype "unspecified"))
      (node (ref "U20") (pin "2") (pinfunction "2_2") (pintype "unspecified"))
      (node (ref "U25") (pin "2") (pinfunction "2_2") (pintype "unspecified"))
      (node (ref "U26") (pin "2") (pinfunction "2_2") (pintype "unspecified"))
      (node (ref "U27") (pin "1") (pinfunction "1_1") (pintype "unspecified"))
      (node (ref "U28") (pin "1") (pinfunction "1_1") (pintype "unspecified"))
      (node (ref "U9") (pin "20") (pinfunction "VCC_20") (pintype "unspecified"))
    )
    (net (code "56") (name "VCC_BAT") (class "Default")
      (node (ref "U1") (pin "1") (pinfunction "VBAT_1") (pintype "unspecified"))
      (node (ref "U13") (pin "1") (pinfunction "1_1") (pintype "unspecified"))
      (node (ref "U23") (pin "1") (pinfunction "+_1") (pintype "unspecified"))
      (node (ref "U24") (pin "1") (pinfunction "1_1") (pintype "unspecified"))
    )
    (net (code "57") (name "unconnected-(U2-NC-Pad4)") (class "Default")
      (node (ref "U2") (pin "4") (pinfunction "NC_4") (pintype "unspecified+no_connect"))
    )
    (net (code "58") (name "unconnected-(U10-NC-Pad3)") (class "Default")
      (node (ref "U10") (pin "3") (pinfunction "NC_3") (pintype "unspecified+no_connect"))
    )
    (net (code "59") (name "unconnected-(USB1-EH-Pad6)") (class "Default")
      (node (ref "USB1") (pin "6") (pinfunction "EH_6") (pintype "input+no_connect"))
    )
    (net (code "60") (name "unconnected-(USB1-ID-Pad4)") (class "Default")
      (node (ref "USB1") (pin "4") (pinfunction "ID_4") (pintype "input+no_connect"))
    )
  )
)
